# pdb-12-50.net
KiCad netlist of a schematic drawn in EasyEDA Pro
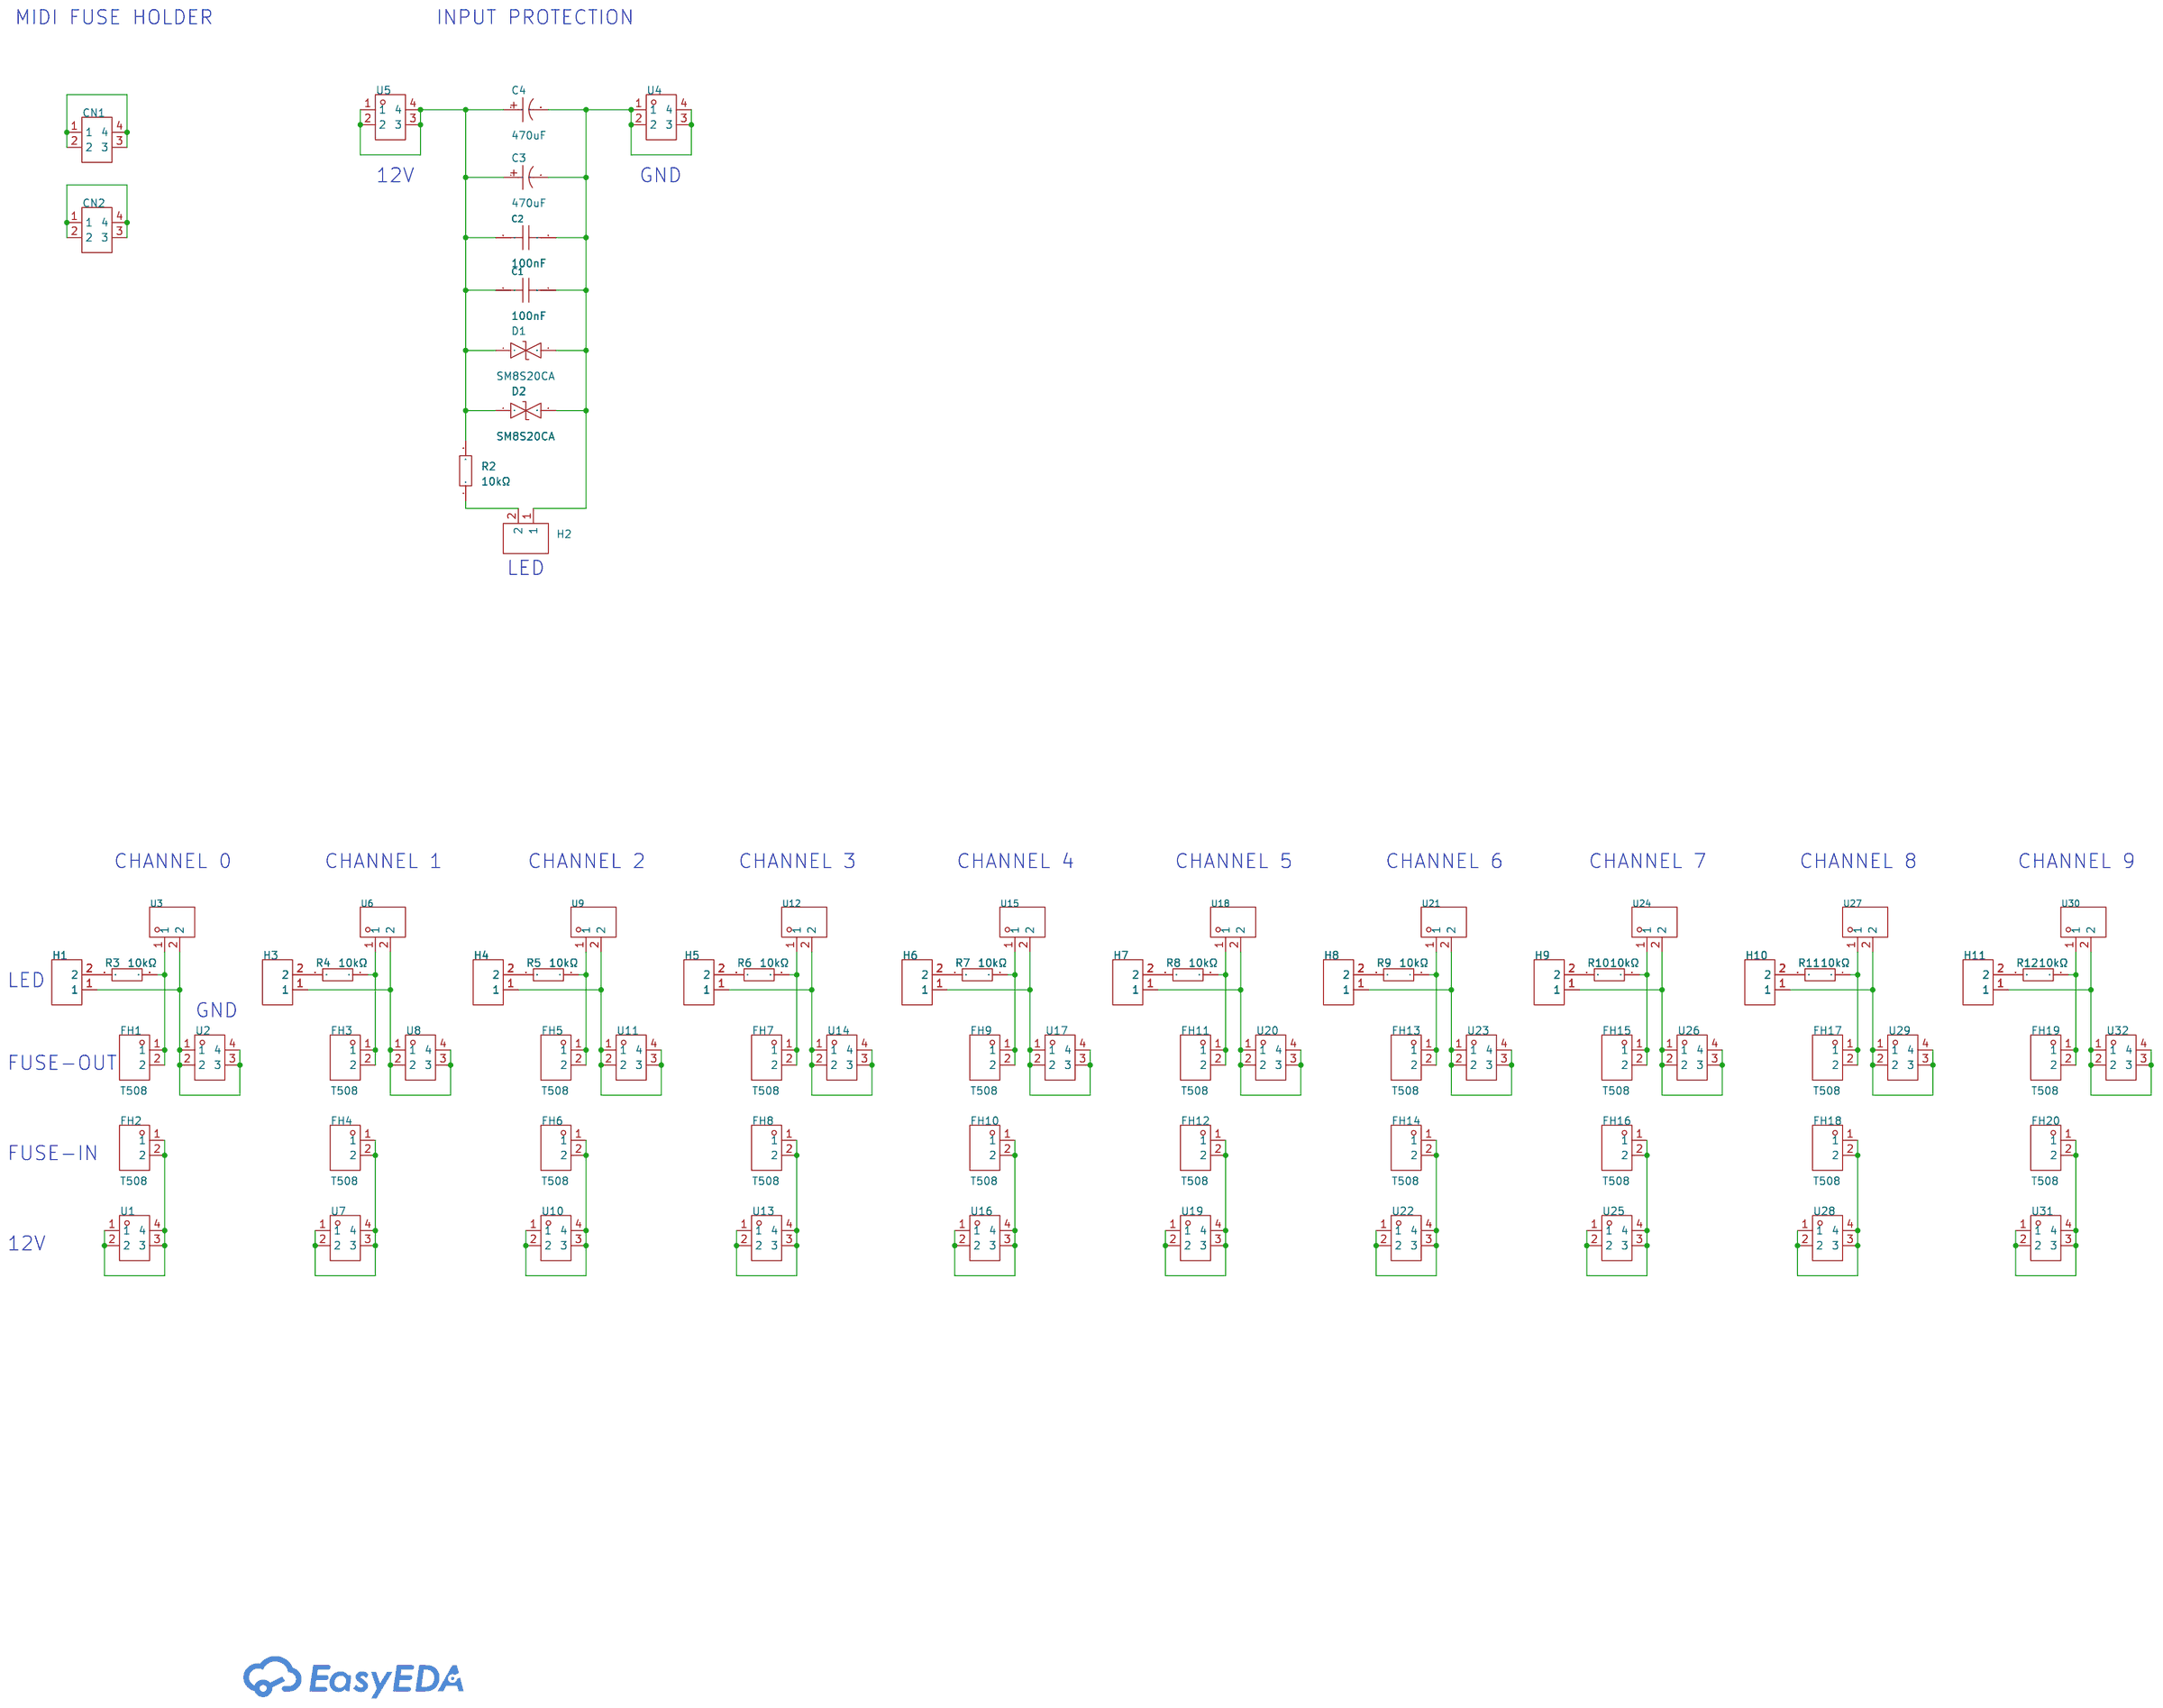
[diagram p0: schematic sheet]

(export (version "E")
  (design (tool "Eeschema 10.0.6"))
  (components
    (comp (ref "C1")
      (value "100nF")
      (footprint "easyedapro:C1210")
      (fields (field (name "Manufacturer Part") "1210B104K501CT") (field (name "Manufacturer") "Walsin(华新科)"))
      (libsource (lib "easyedapro") (part "1210B104K501CT"))
    )
    (comp (ref "C2")
      (value "100nF")
      (footprint "easyedapro:C1210")
      (fields (field (name "Manufacturer Part") "1210B104K501CT") (field (name "Manufacturer") "Walsin(华新科)"))
      (libsource (lib "easyedapro") (part "1210B104K501CT"))
    )
    (comp (ref "C3")
      (value "470uF")
      (footprint "easyedapro:CAP-TH_BD10.0-P5.00-D1.0-FD")
      (fields
        (field (name "Manufacturer Part") "50PX470MEFC10X20")
        (field (name "Manufacturer") "Rubycon(红宝石)")
      )
      (libsource (lib "easyedapro") (part "50PX470MEFC10X20"))
    )
    (comp (ref "C4")
      (value "470uF")
      (footprint "easyedapro:CAP-TH_BD10.0-P5.00-D1.0-FD")
      (fields
        (field (name "Manufacturer Part") "50PX470MEFC10X20")
        (field (name "Manufacturer") "Rubycon(红宝石)")
      )
      (libsource (lib "easyedapro") (part "50PX470MEFC10X20"))
    )
    (comp (ref "CN1")
      (value "1007035CL5")
      (footprint "easyedapro:CONN-TH_4P-L10.5-W10.0_1007035CL5")
      (fields (field (name "Manufacturer") "SAMZO(三佐)"))
      (libsource (lib "easyedapro") (part "1007035CL5"))
    )
    (comp (ref "CN2")
      (value "1007035CL5")
      (footprint "easyedapro:CONN-TH_4P-L10.5-W10.0_1007035CL5")
      (fields (field (name "Manufacturer") "SAMZO(三佐)"))
      (libsource (lib "easyedapro") (part "1007035CL5"))
    )
    (comp (ref "D1")
      (value "SM8S20CA")
      (footprint "easyedapro:DO-218AB_L13.5-W8.4-LS15.5-BI")
      (fields (field (name "Manufacturer") "DOWO(东沃)"))
      (libsource (lib "easyedapro") (part "SM8S20CA"))
    )
    (comp (ref "D2")
      (value "SM8S20CA")
      (footprint "easyedapro:DO-218AB_L13.5-W8.4-LS15.5-BI")
      (fields (field (name "Manufacturer") "DOWO(东沃)"))
      (libsource (lib "easyedapro") (part "SM8S20CA"))
    )
    (comp (ref "FH1")
      (value "T508")
      (footprint "easyedapro:CONN-TH_T508")
      (description "Current Rating:30A")
      (fields (field (name "Manufacturer") "XFCN(兴飞)"))
      (libsource (lib "easyedapro") (part "T508"))
    )
    (comp (ref "FH2")
      (value "T508")
      (footprint "easyedapro:CONN-TH_T508")
      (description "Current Rating:30A")
      (fields (field (name "Manufacturer") "XFCN(兴飞)"))
      (libsource (lib "easyedapro") (part "T508"))
    )
    (comp (ref "FH3")
      (value "T508")
      (footprint "easyedapro:CONN-TH_T508")
      (description "Current Rating:30A")
      (fields (field (name "Manufacturer") "XFCN(兴飞)"))
      (libsource (lib "easyedapro") (part "T508"))
    )
    (comp (ref "FH4")
      (value "T508")
      (footprint "easyedapro:CONN-TH_T508")
      (description "Current Rating:30A")
      (fields (field (name "Manufacturer") "XFCN(兴飞)"))
      (libsource (lib "easyedapro") (part "T508"))
    )
    (comp (ref "FH5")
      (value "T508")
      (footprint "easyedapro:CONN-TH_T508")
      (description "Current Rating:30A")
      (fields (field (name "Manufacturer") "XFCN(兴飞)"))
      (libsource (lib "easyedapro") (part "T508"))
    )
    (comp (ref "FH6")
      (value "T508")
      (footprint "easyedapro:CONN-TH_T508")
      (description "Current Rating:30A")
      (fields (field (name "Manufacturer") "XFCN(兴飞)"))
      (libsource (lib "easyedapro") (part "T508"))
    )
    (comp (ref "FH7")
      (value "T508")
      (footprint "easyedapro:CONN-TH_T508")
      (description "Current Rating:30A")
      (fields (field (name "Manufacturer") "XFCN(兴飞)"))
      (libsource (lib "easyedapro") (part "T508"))
    )
    (comp (ref "FH8")
      (value "T508")
      (footprint "easyedapro:CONN-TH_T508")
      (description "Current Rating:30A")
      (fields (field (name "Manufacturer") "XFCN(兴飞)"))
      (libsource (lib "easyedapro") (part "T508"))
    )
    (comp (ref "FH9")
      (value "T508")
      (footprint "easyedapro:CONN-TH_T508")
      (description "Current Rating:30A")
      (fields (field (name "Manufacturer") "XFCN(兴飞)"))
      (libsource (lib "easyedapro") (part "T508"))
    )
    (comp (ref "FH10")
      (value "T508")
      (footprint "easyedapro:CONN-TH_T508")
      (description "Current Rating:30A")
      (fields (field (name "Manufacturer") "XFCN(兴飞)"))
      (libsource (lib "easyedapro") (part "T508"))
    )
    (comp (ref "FH11")
      (value "T508")
      (footprint "easyedapro:CONN-TH_T508")
      (description "Current Rating:30A")
      (fields (field (name "Manufacturer") "XFCN(兴飞)"))
      (libsource (lib "easyedapro") (part "T508"))
    )
    (comp (ref "FH12")
      (value "T508")
      (footprint "easyedapro:CONN-TH_T508")
      (description "Current Rating:30A")
      (fields (field (name "Manufacturer") "XFCN(兴飞)"))
      (libsource (lib "easyedapro") (part "T508"))
    )
    (comp (ref "FH13")
      (value "T508")
      (footprint "easyedapro:CONN-TH_T508")
      (description "Current Rating:30A")
      (fields (field (name "Manufacturer") "XFCN(兴飞)"))
      (libsource (lib "easyedapro") (part "T508"))
    )
    (comp (ref "FH14")
      (value "T508")
      (footprint "easyedapro:CONN-TH_T508")
      (description "Current Rating:30A")
      (fields (field (name "Manufacturer") "XFCN(兴飞)"))
      (libsource (lib "easyedapro") (part "T508"))
    )
    (comp (ref "FH15")
      (value "T508")
      (footprint "easyedapro:CONN-TH_T508")
      (description "Current Rating:30A")
      (fields (field (name "Manufacturer") "XFCN(兴飞)"))
      (libsource (lib "easyedapro") (part "T508"))
    )
    (comp (ref "FH16")
      (value "T508")
      (footprint "easyedapro:CONN-TH_T508")
      (description "Current Rating:30A")
      (fields (field (name "Manufacturer") "XFCN(兴飞)"))
      (libsource (lib "easyedapro") (part "T508"))
    )
    (comp (ref "FH17")
      (value "T508")
      (footprint "easyedapro:CONN-TH_T508")
      (description "Current Rating:30A")
      (fields (field (name "Manufacturer") "XFCN(兴飞)"))
      (libsource (lib "easyedapro") (part "T508"))
    )
    (comp (ref "FH18")
      (value "T508")
      (footprint "easyedapro:CONN-TH_T508")
      (description "Current Rating:30A")
      (fields (field (name "Manufacturer") "XFCN(兴飞)"))
      (libsource (lib "easyedapro") (part "T508"))
    )
    (comp (ref "FH19")
      (value "T508")
      (footprint "easyedapro:CONN-TH_T508")
      (description "Current Rating:30A")
      (fields (field (name "Manufacturer") "XFCN(兴飞)"))
      (libsource (lib "easyedapro") (part "T508"))
    )
    (comp (ref "FH20")
      (value "T508")
      (footprint "easyedapro:CONN-TH_T508")
      (description "Current Rating:30A")
      (fields (field (name "Manufacturer") "XFCN(兴飞)"))
      (libsource (lib "easyedapro") (part "T508"))
    )
    (comp (ref "H1")
      (value "PZ254V-11-02P")
      (footprint "easyedapro:HDR-TH_2P-P2.54-V-M")
      (fields (field (name "Manufacturer") "XFCN(兴飞)"))
      (libsource (lib "easyedapro") (part "PZ254V-11-02P"))
    )
    (comp (ref "H2")
      (value "PZ254V-11-02P")
      (footprint "easyedapro:HDR-TH_2P-P2.54-V-M")
      (fields (field (name "Manufacturer") "XFCN(兴飞)"))
      (libsource (lib "easyedapro") (part "PZ254V-11-02P"))
    )
    (comp (ref "H3")
      (value "PZ254V-11-02P")
      (footprint "easyedapro:HDR-TH_2P-P2.54-V-M")
      (fields (field (name "Manufacturer") "XFCN(兴飞)"))
      (libsource (lib "easyedapro") (part "PZ254V-11-02P"))
    )
    (comp (ref "H4")
      (value "PZ254V-11-02P")
      (footprint "easyedapro:HDR-TH_2P-P2.54-V-M")
      (fields (field (name "Manufacturer") "XFCN(兴飞)"))
      (libsource (lib "easyedapro") (part "PZ254V-11-02P"))
    )
    (comp (ref "H5")
      (value "PZ254V-11-02P")
      (footprint "easyedapro:HDR-TH_2P-P2.54-V-M")
      (fields (field (name "Manufacturer") "XFCN(兴飞)"))
      (libsource (lib "easyedapro") (part "PZ254V-11-02P"))
    )
    (comp (ref "H6")
      (value "PZ254V-11-02P")
      (footprint "easyedapro:HDR-TH_2P-P2.54-V-M")
      (fields (field (name "Manufacturer") "XFCN(兴飞)"))
      (libsource (lib "easyedapro") (part "PZ254V-11-02P"))
    )
    (comp (ref "H7")
      (value "PZ254V-11-02P")
      (footprint "easyedapro:HDR-TH_2P-P2.54-V-M")
      (fields (field (name "Manufacturer") "XFCN(兴飞)"))
      (libsource (lib "easyedapro") (part "PZ254V-11-02P"))
    )
    (comp (ref "H8")
      (value "PZ254V-11-02P")
      (footprint "easyedapro:HDR-TH_2P-P2.54-V-M")
      (fields (field (name "Manufacturer") "XFCN(兴飞)"))
      (libsource (lib "easyedapro") (part "PZ254V-11-02P"))
    )
    (comp (ref "H9")
      (value "PZ254V-11-02P")
      (footprint "easyedapro:HDR-TH_2P-P2.54-V-M")
      (fields (field (name "Manufacturer") "XFCN(兴飞)"))
      (libsource (lib "easyedapro") (part "PZ254V-11-02P"))
    )
    (comp (ref "H10")
      (value "PZ254V-11-02P")
      (footprint "easyedapro:HDR-TH_2P-P2.54-V-M")
      (fields (field (name "Manufacturer") "XFCN(兴飞)"))
      (libsource (lib "easyedapro") (part "PZ254V-11-02P"))
    )
    (comp (ref "H11")
      (value "PZ254V-11-02P")
      (footprint "easyedapro:HDR-TH_2P-P2.54-V-M")
      (fields (field (name "Manufacturer") "XFCN(兴飞)"))
      (libsource (lib "easyedapro") (part "PZ254V-11-02P"))
    )
    (comp (ref "R2")
      (value "10kΩ")
      (footprint "easyedapro:RES-TH_BD1.8-L3.2-P7.20-D0.4")
      (fields
        (field (name "Manufacturer Part") "1206W4F1002T5E")
        (field (name "Manufacturer") "UNI-ROYAL(厚声)")
      )
      (libsource (lib "easyedapro") (part "Res"))
    )
    (comp (ref "R3")
      (value "10kΩ")
      (footprint "easyedapro:RES-TH_BD1.8-L3.2-P7.20-D0.4")
      (fields
        (field (name "Manufacturer Part") "1206W4F1002T5E")
        (field (name "Manufacturer") "UNI-ROYAL(厚声)")
      )
      (libsource (lib "easyedapro") (part "Res"))
    )
    (comp (ref "R4")
      (value "10kΩ")
      (footprint "easyedapro:RES-TH_BD1.8-L3.2-P7.20-D0.4")
      (fields
        (field (name "Manufacturer Part") "1206W4F1002T5E")
        (field (name "Manufacturer") "UNI-ROYAL(厚声)")
      )
      (libsource (lib "easyedapro") (part "Res"))
    )
    (comp (ref "R5")
      (value "10kΩ")
      (footprint "easyedapro:RES-TH_BD1.8-L3.2-P7.20-D0.4")
      (fields
        (field (name "Manufacturer Part") "1206W4F1002T5E")
        (field (name "Manufacturer") "UNI-ROYAL(厚声)")
      )
      (libsource (lib "easyedapro") (part "Res"))
    )
    (comp (ref "R6")
      (value "10kΩ")
      (footprint "easyedapro:RES-TH_BD1.8-L3.2-P7.20-D0.4")
      (fields
        (field (name "Manufacturer Part") "1206W4F1002T5E")
        (field (name "Manufacturer") "UNI-ROYAL(厚声)")
      )
      (libsource (lib "easyedapro") (part "Res"))
    )
    (comp (ref "R7")
      (value "10kΩ")
      (footprint "easyedapro:RES-TH_BD1.8-L3.2-P7.20-D0.4")
      (fields
        (field (name "Manufacturer Part") "1206W4F1002T5E")
        (field (name "Manufacturer") "UNI-ROYAL(厚声)")
      )
      (libsource (lib "easyedapro") (part "Res"))
    )
    (comp (ref "R8")
      (value "10kΩ")
      (footprint "easyedapro:RES-TH_BD1.8-L3.2-P7.20-D0.4")
      (fields
        (field (name "Manufacturer Part") "1206W4F1002T5E")
        (field (name "Manufacturer") "UNI-ROYAL(厚声)")
      )
      (libsource (lib "easyedapro") (part "Res"))
    )
    (comp (ref "R9")
      (value "10kΩ")
      (footprint "easyedapro:RES-TH_BD1.8-L3.2-P7.20-D0.4")
      (fields
        (field (name "Manufacturer Part") "1206W4F1002T5E")
        (field (name "Manufacturer") "UNI-ROYAL(厚声)")
      )
      (libsource (lib "easyedapro") (part "Res"))
    )
    (comp (ref "R10")
      (value "10kΩ")
      (footprint "easyedapro:RES-TH_BD1.8-L3.2-P7.20-D0.4")
      (fields
        (field (name "Manufacturer Part") "1206W4F1002T5E")
        (field (name "Manufacturer") "UNI-ROYAL(厚声)")
      )
      (libsource (lib "easyedapro") (part "Res"))
    )
    (comp (ref "R11")
      (value "10kΩ")
      (footprint "easyedapro:RES-TH_BD1.8-L3.2-P7.20-D0.4")
      (fields
        (field (name "Manufacturer Part") "1206W4F1002T5E")
        (field (name "Manufacturer") "UNI-ROYAL(厚声)")
      )
      (libsource (lib "easyedapro") (part "Res"))
    )
    (comp (ref "R12")
      (value "10kΩ")
      (footprint "easyedapro:RES-TH_BD1.8-L3.2-P7.20-D0.4")
      (fields
        (field (name "Manufacturer Part") "1206W4F1002T5E")
        (field (name "Manufacturer") "UNI-ROYAL(厚声)")
      )
      (libsource (lib "easyedapro") (part "Res"))
    )
    (comp (ref "U1")
      (value "66540S0M3")
      (footprint "easyedapro:SMD_66540S0M3")
      (fields (field (name "Manufacturer") "SAMZO(三佐)"))
      (libsource (lib "easyedapro") (part "66540S0M3"))
    )
    (comp (ref "U2")
      (value "66540S0M3")
      (footprint "easyedapro:SMD_66540S0M3")
      (fields (field (name "Manufacturer") "SAMZO(三佐)"))
      (libsource (lib "easyedapro") (part "66540S0M3"))
    )
    (comp (ref "U3")
      (value "KF635-6.35-2P")
      (footprint "easyedapro:CONN-TH_P6.35_KF635-6.35-2P")
      (fields (field (name "Manufacturer") "KEFA(科发)"))
      (libsource (lib "easyedapro") (part "KF635-6.35-2P"))
    )
    (comp (ref "U4")
      (value "66540S0M3")
      (footprint "easyedapro:SMD_66540S0M3")
      (fields (field (name "Manufacturer") "SAMZO(三佐)"))
      (libsource (lib "easyedapro") (part "66540S0M3"))
    )
    (comp (ref "U5")
      (value "66540S0M3")
      (footprint "easyedapro:SMD_66540S0M3")
      (fields (field (name "Manufacturer") "SAMZO(三佐)"))
      (libsource (lib "easyedapro") (part "66540S0M3"))
    )
    (comp (ref "U6")
      (value "KF635-6.35-2P")
      (footprint "easyedapro:CONN-TH_P6.35_KF635-6.35-2P")
      (fields (field (name "Manufacturer") "KEFA(科发)"))
      (libsource (lib "easyedapro") (part "KF635-6.35-2P"))
    )
    (comp (ref "U7")
      (value "66540S0M3")
      (footprint "easyedapro:SMD_66540S0M3")
      (fields (field (name "Manufacturer") "SAMZO(三佐)"))
      (libsource (lib "easyedapro") (part "66540S0M3"))
    )
    (comp (ref "U8")
      (value "66540S0M3")
      (footprint "easyedapro:SMD_66540S0M3")
      (fields (field (name "Manufacturer") "SAMZO(三佐)"))
      (libsource (lib "easyedapro") (part "66540S0M3"))
    )
    (comp (ref "U9")
      (value "KF635-6.35-2P")
      (footprint "easyedapro:CONN-TH_P6.35_KF635-6.35-2P")
      (fields (field (name "Manufacturer") "KEFA(科发)"))
      (libsource (lib "easyedapro") (part "KF635-6.35-2P"))
    )
    (comp (ref "U10")
      (value "66540S0M3")
      (footprint "easyedapro:SMD_66540S0M3")
      (fields (field (name "Manufacturer") "SAMZO(三佐)"))
      (libsource (lib "easyedapro") (part "66540S0M3"))
    )
    (comp (ref "U11")
      (value "66540S0M3")
      (footprint "easyedapro:SMD_66540S0M3")
      (fields (field (name "Manufacturer") "SAMZO(三佐)"))
      (libsource (lib "easyedapro") (part "66540S0M3"))
    )
    (comp (ref "U12")
      (value "KF635-6.35-2P")
      (footprint "easyedapro:CONN-TH_P6.35_KF635-6.35-2P")
      (fields (field (name "Manufacturer") "KEFA(科发)"))
      (libsource (lib "easyedapro") (part "KF635-6.35-2P"))
    )
    (comp (ref "U13")
      (value "66540S0M3")
      (footprint "easyedapro:SMD_66540S0M3")
      (fields (field (name "Manufacturer") "SAMZO(三佐)"))
      (libsource (lib "easyedapro") (part "66540S0M3"))
    )
    (comp (ref "U14")
      (value "66540S0M3")
      (footprint "easyedapro:SMD_66540S0M3")
      (fields (field (name "Manufacturer") "SAMZO(三佐)"))
      (libsource (lib "easyedapro") (part "66540S0M3"))
    )
    (comp (ref "U15")
      (value "KF635-6.35-2P")
      (footprint "easyedapro:CONN-TH_P6.35_KF635-6.35-2P")
      (fields (field (name "Manufacturer") "KEFA(科发)"))
      (libsource (lib "easyedapro") (part "KF635-6.35-2P"))
    )
    (comp (ref "U16")
      (value "66540S0M3")
      (footprint "easyedapro:SMD_66540S0M3")
      (fields (field (name "Manufacturer") "SAMZO(三佐)"))
      (libsource (lib "easyedapro") (part "66540S0M3"))
    )
    (comp (ref "U17")
      (value "66540S0M3")
      (footprint "easyedapro:SMD_66540S0M3")
      (fields (field (name "Manufacturer") "SAMZO(三佐)"))
      (libsource (lib "easyedapro") (part "66540S0M3"))
    )
    (comp (ref "U18")
      (value "KF635-6.35-2P")
      (footprint "easyedapro:CONN-TH_P6.35_KF635-6.35-2P")
      (fields (field (name "Manufacturer") "KEFA(科发)"))
      (libsource (lib "easyedapro") (part "KF635-6.35-2P"))
    )
    (comp (ref "U19")
      (value "66540S0M3")
      (footprint "easyedapro:SMD_66540S0M3")
      (fields (field (name "Manufacturer") "SAMZO(三佐)"))
      (libsource (lib "easyedapro") (part "66540S0M3"))
    )
    (comp (ref "U20")
      (value "66540S0M3")
      (footprint "easyedapro:SMD_66540S0M3")
      (fields (field (name "Manufacturer") "SAMZO(三佐)"))
      (libsource (lib "easyedapro") (part "66540S0M3"))
    )
    (comp (ref "U21")
      (value "KF635-6.35-2P")
      (footprint "easyedapro:CONN-TH_P6.35_KF635-6.35-2P")
      (fields (field (name "Manufacturer") "KEFA(科发)"))
      (libsource (lib "easyedapro") (part "KF635-6.35-2P"))
    )
    (comp (ref "U22")
      (value "66540S0M3")
      (footprint "easyedapro:SMD_66540S0M3")
      (fields (field (name "Manufacturer") "SAMZO(三佐)"))
      (libsource (lib "easyedapro") (part "66540S0M3"))
    )
    (comp (ref "U23")
      (value "66540S0M3")
      (footprint "easyedapro:SMD_66540S0M3")
      (fields (field (name "Manufacturer") "SAMZO(三佐)"))
      (libsource (lib "easyedapro") (part "66540S0M3"))
    )
    (comp (ref "U24")
      (value "KF635-6.35-2P")
      (footprint "easyedapro:CONN-TH_P6.35_KF635-6.35-2P")
      (fields (field (name "Manufacturer") "KEFA(科发)"))
      (libsource (lib "easyedapro") (part "KF635-6.35-2P"))
    )
    (comp (ref "U25")
      (value "66540S0M3")
      (footprint "easyedapro:SMD_66540S0M3")
      (fields (field (name "Manufacturer") "SAMZO(三佐)"))
      (libsource (lib "easyedapro") (part "66540S0M3"))
    )
    (comp (ref "U26")
      (value "66540S0M3")
      (footprint "easyedapro:SMD_66540S0M3")
      (fields (field (name "Manufacturer") "SAMZO(三佐)"))
      (libsource (lib "easyedapro") (part "66540S0M3"))
    )
    (comp (ref "U27")
      (value "KF635-6.35-2P")
      (footprint "easyedapro:CONN-TH_P6.35_KF635-6.35-2P")
      (fields (field (name "Manufacturer") "KEFA(科发)"))
      (libsource (lib "easyedapro") (part "KF635-6.35-2P"))
    )
    (comp (ref "U28")
      (value "66540S0M3")
      (footprint "easyedapro:SMD_66540S0M3")
      (fields (field (name "Manufacturer") "SAMZO(三佐)"))
      (libsource (lib "easyedapro") (part "66540S0M3"))
    )
    (comp (ref "U29")
      (value "66540S0M3")
      (footprint "easyedapro:SMD_66540S0M3")
      (fields (field (name "Manufacturer") "SAMZO(三佐)"))
      (libsource (lib "easyedapro") (part "66540S0M3"))
    )
    (comp (ref "U30")
      (value "KF635-6.35-2P")
      (footprint "easyedapro:CONN-TH_P6.35_KF635-6.35-2P")
      (fields (field (name "Manufacturer") "KEFA(科发)"))
      (libsource (lib "easyedapro") (part "KF635-6.35-2P"))
    )
    (comp (ref "U31")
      (value "66540S0M3")
      (footprint "easyedapro:SMD_66540S0M3")
      (fields (field (name "Manufacturer") "SAMZO(三佐)"))
      (libsource (lib "easyedapro") (part "66540S0M3"))
    )
    (comp (ref "U32")
      (value "66540S0M3")
      (footprint "easyedapro:SMD_66540S0M3")
      (fields (field (name "Manufacturer") "SAMZO(三佐)"))
      (libsource (lib "easyedapro") (part "66540S0M3"))
    )
  )
  (nets
    (net (code "1") (name "Net-(C1-Pad1)") (class "Default")
      (node (ref "C1") (pin "1") (pinfunction "1_1") (pintype "input"))
      (node (ref "C2") (pin "1") (pinfunction "1_1") (pintype "input"))
      (node (ref "C3") (pin "2") (pinfunction "2_2") (pintype "input"))
      (node (ref "C4") (pin "2") (pinfunction "2_2") (pintype "input"))
      (node (ref "D1") (pin "2") (pinfunction "2_2") (pintype "unspecified"))
      (node (ref "D2") (pin "2") (pinfunction "2_2") (pintype "unspecified"))
      (node (ref "H2") (pin "1") (pinfunction "1_1") (pintype "unspecified"))
      (node (ref "U4") (pin "1") (pinfunction "1_1") (pintype "unspecified"))
      (node (ref "U4") (pin "2") (pinfunction "2_2") (pintype "unspecified"))
      (node (ref "U4") (pin "3") (pinfunction "3_3") (pintype "unspecified"))
      (node (ref "U4") (pin "4") (pinfunction "4_4") (pintype "unspecified"))
    )
    (net (code "2") (name "Net-(C1-Pad2)") (class "Default")
      (node (ref "C1") (pin "2") (pinfunction "2_2") (pintype "input"))
      (node (ref "C2") (pin "2") (pinfunction "2_2") (pintype "input"))
      (node (ref "C3") (pin "1") (pinfunction "1_1") (pintype "input"))
      (node (ref "C4") (pin "1") (pinfunction "1_1") (pintype "input"))
      (node (ref "D1") (pin "1") (pinfunction "1_1") (pintype "unspecified"))
      (node (ref "D2") (pin "1") (pinfunction "1_1") (pintype "unspecified"))
      (node (ref "R2") (pin "2") (pinfunction "2_2") (pintype "input"))
      (node (ref "U5") (pin "1") (pinfunction "1_1") (pintype "unspecified"))
      (node (ref "U5") (pin "2") (pinfunction "2_2") (pintype "unspecified"))
      (node (ref "U5") (pin "3") (pinfunction "3_3") (pintype "unspecified"))
      (node (ref "U5") (pin "4") (pinfunction "4_4") (pintype "unspecified"))
    )
    (net (code "3") (name "Net-(CN1-Pad1)") (class "Default")
      (node (ref "CN1") (pin "1") (pinfunction "1_1") (pintype "unspecified"))
      (node (ref "CN1") (pin "2") (pinfunction "2_2") (pintype "unspecified"))
      (node (ref "CN1") (pin "3") (pinfunction "3_3") (pintype "unspecified"))
      (node (ref "CN1") (pin "4") (pinfunction "4_4") (pintype "unspecified"))
    )
    (net (code "4") (name "Net-(CN2-Pad1)") (class "Default")
      (node (ref "CN2") (pin "1") (pinfunction "1_1") (pintype "unspecified"))
      (node (ref "CN2") (pin "2") (pinfunction "2_2") (pintype "unspecified"))
      (node (ref "CN2") (pin "3") (pinfunction "3_3") (pintype "unspecified"))
      (node (ref "CN2") (pin "4") (pinfunction "4_4") (pintype "unspecified"))
    )
    (net (code "5") (name "Net-(FH1-Pad1)") (class "Default")
      (node (ref "FH1") (pin "1") (pinfunction "1_1") (pintype "unspecified"))
      (node (ref "FH1") (pin "2") (pinfunction "2_2") (pintype "unspecified"))
      (node (ref "R3") (pin "1") (pinfunction "1_1") (pintype "input"))
      (node (ref "U3") (pin "1") (pinfunction "1_1") (pintype "input"))
    )
    (net (code "6") (name "Net-(FH2-Pad1)") (class "Default")
      (node (ref "FH2") (pin "1") (pinfunction "1_1") (pintype "unspecified"))
      (node (ref "FH2") (pin "2") (pinfunction "2_2") (pintype "unspecified"))
      (node (ref "U1") (pin "1") (pinfunction "1_1") (pintype "unspecified"))
      (node (ref "U1") (pin "2") (pinfunction "2_2") (pintype "unspecified"))
      (node (ref "U1") (pin "3") (pinfunction "3_3") (pintype "unspecified"))
      (node (ref "U1") (pin "4") (pinfunction "4_4") (pintype "unspecified"))
    )
    (net (code "7") (name "Net-(FH3-Pad1)") (class "Default")
      (node (ref "FH3") (pin "1") (pinfunction "1_1") (pintype "unspecified"))
      (node (ref "FH3") (pin "2") (pinfunction "2_2") (pintype "unspecified"))
      (node (ref "R4") (pin "1") (pinfunction "1_1") (pintype "input"))
      (node (ref "U6") (pin "1") (pinfunction "1_1") (pintype "input"))
    )
    (net (code "8") (name "Net-(FH4-Pad1)") (class "Default")
      (node (ref "FH4") (pin "1") (pinfunction "1_1") (pintype "unspecified"))
      (node (ref "FH4") (pin "2") (pinfunction "2_2") (pintype "unspecified"))
      (node (ref "U7") (pin "1") (pinfunction "1_1") (pintype "unspecified"))
      (node (ref "U7") (pin "2") (pinfunction "2_2") (pintype "unspecified"))
      (node (ref "U7") (pin "3") (pinfunction "3_3") (pintype "unspecified"))
      (node (ref "U7") (pin "4") (pinfunction "4_4") (pintype "unspecified"))
    )
    (net (code "9") (name "Net-(FH5-Pad1)") (class "Default")
      (node (ref "FH5") (pin "1") (pinfunction "1_1") (pintype "unspecified"))
      (node (ref "FH5") (pin "2") (pinfunction "2_2") (pintype "unspecified"))
      (node (ref "R5") (pin "1") (pinfunction "1_1") (pintype "input"))
      (node (ref "U9") (pin "1") (pinfunction "1_1") (pintype "input"))
    )
    (net (code "10") (name "Net-(FH6-Pad1)") (class "Default")
      (node (ref "FH6") (pin "1") (pinfunction "1_1") (pintype "unspecified"))
      (node (ref "FH6") (pin "2") (pinfunction "2_2") (pintype "unspecified"))
      (node (ref "U10") (pin "1") (pinfunction "1_1") (pintype "unspecified"))
      (node (ref "U10") (pin "2") (pinfunction "2_2") (pintype "unspecified"))
      (node (ref "U10") (pin "3") (pinfunction "3_3") (pintype "unspecified"))
      (node (ref "U10") (pin "4") (pinfunction "4_4") (pintype "unspecified"))
    )
    (net (code "11") (name "Net-(FH7-Pad1)") (class "Default")
      (node (ref "FH7") (pin "1") (pinfunction "1_1") (pintype "unspecified"))
      (node (ref "FH7") (pin "2") (pinfunction "2_2") (pintype "unspecified"))
      (node (ref "R6") (pin "1") (pinfunction "1_1") (pintype "input"))
      (node (ref "U12") (pin "1") (pinfunction "1_1") (pintype "input"))
    )
    (net (code "12") (name "Net-(FH8-Pad1)") (class "Default")
      (node (ref "FH8") (pin "1") (pinfunction "1_1") (pintype "unspecified"))
      (node (ref "FH8") (pin "2") (pinfunction "2_2") (pintype "unspecified"))
      (node (ref "U13") (pin "1") (pinfunction "1_1") (pintype "unspecified"))
      (node (ref "U13") (pin "2") (pinfunction "2_2") (pintype "unspecified"))
      (node (ref "U13") (pin "3") (pinfunction "3_3") (pintype "unspecified"))
      (node (ref "U13") (pin "4") (pinfunction "4_4") (pintype "unspecified"))
    )
    (net (code "13") (name "Net-(FH9-Pad1)") (class "Default")
      (node (ref "FH9") (pin "1") (pinfunction "1_1") (pintype "unspecified"))
      (node (ref "FH9") (pin "2") (pinfunction "2_2") (pintype "unspecified"))
      (node (ref "R7") (pin "1") (pinfunction "1_1") (pintype "input"))
      (node (ref "U15") (pin "1") (pinfunction "1_1") (pintype "input"))
    )
    (net (code "14") (name "Net-(FH10-Pad1)") (class "Default")
      (node (ref "FH10") (pin "1") (pinfunction "1_1") (pintype "unspecified"))
      (node (ref "FH10") (pin "2") (pinfunction "2_2") (pintype "unspecified"))
      (node (ref "U16") (pin "1") (pinfunction "1_1") (pintype "unspecified"))
      (node (ref "U16") (pin "2") (pinfunction "2_2") (pintype "unspecified"))
      (node (ref "U16") (pin "3") (pinfunction "3_3") (pintype "unspecified"))
      (node (ref "U16") (pin "4") (pinfunction "4_4") (pintype "unspecified"))
    )
    (net (code "15") (name "Net-(FH11-Pad1)") (class "Default")
      (node (ref "FH11") (pin "1") (pinfunction "1_1") (pintype "unspecified"))
      (node (ref "FH11") (pin "2") (pinfunction "2_2") (pintype "unspecified"))
      (node (ref "R8") (pin "1") (pinfunction "1_1") (pintype "input"))
      (node (ref "U18") (pin "1") (pinfunction "1_1") (pintype "input"))
    )
    (net (code "16") (name "Net-(FH12-Pad1)") (class "Default")
      (node (ref "FH12") (pin "1") (pinfunction "1_1") (pintype "unspecified"))
      (node (ref "FH12") (pin "2") (pinfunction "2_2") (pintype "unspecified"))
      (node (ref "U19") (pin "1") (pinfunction "1_1") (pintype "unspecified"))
      (node (ref "U19") (pin "2") (pinfunction "2_2") (pintype "unspecified"))
      (node (ref "U19") (pin "3") (pinfunction "3_3") (pintype "unspecified"))
      (node (ref "U19") (pin "4") (pinfunction "4_4") (pintype "unspecified"))
    )
    (net (code "17") (name "Net-(FH13-Pad1)") (class "Default")
      (node (ref "FH13") (pin "1") (pinfunction "1_1") (pintype "unspecified"))
      (node (ref "FH13") (pin "2") (pinfunction "2_2") (pintype "unspecified"))
      (node (ref "R9") (pin "1") (pinfunction "1_1") (pintype "input"))
      (node (ref "U21") (pin "1") (pinfunction "1_1") (pintype "input"))
    )
    (net (code "18") (name "Net-(FH14-Pad1)") (class "Default")
      (node (ref "FH14") (pin "1") (pinfunction "1_1") (pintype "unspecified"))
      (node (ref "FH14") (pin "2") (pinfunction "2_2") (pintype "unspecified"))
      (node (ref "U22") (pin "1") (pinfunction "1_1") (pintype "unspecified"))
      (node (ref "U22") (pin "2") (pinfunction "2_2") (pintype "unspecified"))
      (node (ref "U22") (pin "3") (pinfunction "3_3") (pintype "unspecified"))
      (node (ref "U22") (pin "4") (pinfunction "4_4") (pintype "unspecified"))
    )
    (net (code "19") (name "Net-(FH15-Pad1)") (class "Default")
      (node (ref "FH15") (pin "1") (pinfunction "1_1") (pintype "unspecified"))
      (node (ref "FH15") (pin "2") (pinfunction "2_2") (pintype "unspecified"))
      (node (ref "R10") (pin "1") (pinfunction "1_1") (pintype "input"))
      (node (ref "U24") (pin "1") (pinfunction "1_1") (pintype "input"))
    )
    (net (code "20") (name "Net-(FH16-Pad1)") (class "Default")
      (node (ref "FH16") (pin "1") (pinfunction "1_1") (pintype "unspecified"))
      (node (ref "FH16") (pin "2") (pinfunction "2_2") (pintype "unspecified"))
      (node (ref "U25") (pin "1") (pinfunction "1_1") (pintype "unspecified"))
      (node (ref "U25") (pin "2") (pinfunction "2_2") (pintype "unspecified"))
      (node (ref "U25") (pin "3") (pinfunction "3_3") (pintype "unspecified"))
      (node (ref "U25") (pin "4") (pinfunction "4_4") (pintype "unspecified"))
    )
    (net (code "21") (name "Net-(FH17-Pad1)") (class "Default")
      (node (ref "FH17") (pin "1") (pinfunction "1_1") (pintype "unspecified"))
      (node (ref "FH17") (pin "2") (pinfunction "2_2") (pintype "unspecified"))
      (node (ref "R11") (pin "1") (pinfunction "1_1") (pintype "input"))
      (node (ref "U27") (pin "1") (pinfunction "1_1") (pintype "input"))
    )
    (net (code "22") (name "Net-(FH18-Pad1)") (class "Default")
      (node (ref "FH18") (pin "1") (pinfunction "1_1") (pintype "unspecified"))
      (node (ref "FH18") (pin "2") (pinfunction "2_2") (pintype "unspecified"))
      (node (ref "U28") (pin "1") (pinfunction "1_1") (pintype "unspecified"))
      (node (ref "U28") (pin "2") (pinfunction "2_2") (pintype "unspecified"))
      (node (ref "U28") (pin "3") (pinfunction "3_3") (pintype "unspecified"))
      (node (ref "U28") (pin "4") (pinfunction "4_4") (pintype "unspecified"))
    )
    (net (code "23") (name "Net-(FH19-Pad1)") (class "Default")
      (node (ref "FH19") (pin "1") (pinfunction "1_1") (pintype "unspecified"))
      (node (ref "FH19") (pin "2") (pinfunction "2_2") (pintype "unspecified"))
      (node (ref "R12") (pin "1") (pinfunction "1_1") (pintype "input"))
      (node (ref "U30") (pin "1") (pinfunction "1_1") (pintype "input"))
    )
    (net (code "24") (name "Net-(FH20-Pad1)") (class "Default")
      (node (ref "FH20") (pin "1") (pinfunction "1_1") (pintype "unspecified"))
      (node (ref "FH20") (pin "2") (pinfunction "2_2") (pintype "unspecified"))
      (node (ref "U31") (pin "1") (pinfunction "1_1") (pintype "unspecified"))
      (node (ref "U31") (pin "2") (pinfunction "2_2") (pintype "unspecified"))
      (node (ref "U31") (pin "3") (pinfunction "3_3") (pintype "unspecified"))
      (node (ref "U31") (pin "4") (pinfunction "4_4") (pintype "unspecified"))
    )
    (net (code "25") (name "Net-(H1-Pad1)") (class "Default")
      (node (ref "H1") (pin "1") (pinfunction "1_1") (pintype "unspecified"))
      (node (ref "U2") (pin "1") (pinfunction "1_1") (pintype "unspecified"))
      (node (ref "U2") (pin "2") (pinfunction "2_2") (pintype "unspecified"))
      (node (ref "U2") (pin "3") (pinfunction "3_3") (pintype "unspecified"))
      (node (ref "U2") (pin "4") (pinfunction "4_4") (pintype "unspecified"))
      (node (ref "U3") (pin "2") (pinfunction "2_2") (pintype "input"))
    )
    (net (code "26") (name "Net-(H1-Pad2)") (class "Default")
      (node (ref "H1") (pin "2") (pinfunction "2_2") (pintype "unspecified"))
      (node (ref "R3") (pin "2") (pinfunction "2_2") (pintype "input"))
    )
    (net (code "27") (name "Net-(H2-Pad2)") (class "Default")
      (node (ref "H2") (pin "2") (pinfunction "2_2") (pintype "unspecified"))
      (node (ref "R2") (pin "1") (pinfunction "1_1") (pintype "input"))
    )
    (net (code "28") (name "Net-(H3-Pad1)") (class "Default")
      (node (ref "H3") (pin "1") (pinfunction "1_1") (pintype "unspecified"))
      (node (ref "U6") (pin "2") (pinfunction "2_2") (pintype "input"))
      (node (ref "U8") (pin "1") (pinfunction "1_1") (pintype "unspecified"))
      (node (ref "U8") (pin "2") (pinfunction "2_2") (pintype "unspecified"))
      (node (ref "U8") (pin "3") (pinfunction "3_3") (pintype "unspecified"))
      (node (ref "U8") (pin "4") (pinfunction "4_4") (pintype "unspecified"))
    )
    (net (code "29") (name "Net-(H3-Pad2)") (class "Default")
      (node (ref "H3") (pin "2") (pinfunction "2_2") (pintype "unspecified"))
      (node (ref "R4") (pin "2") (pinfunction "2_2") (pintype "input"))
    )
    (net (code "30") (name "Net-(H4-Pad1)") (class "Default")
      (node (ref "H4") (pin "1") (pinfunction "1_1") (pintype "unspecified"))
      (node (ref "U11") (pin "1") (pinfunction "1_1") (pintype "unspecified"))
      (node (ref "U11") (pin "2") (pinfunction "2_2") (pintype "unspecified"))
      (node (ref "U11") (pin "3") (pinfunction "3_3") (pintype "unspecified"))
      (node (ref "U11") (pin "4") (pinfunction "4_4") (pintype "unspecified"))
      (node (ref "U9") (pin "2") (pinfunction "2_2") (pintype "input"))
    )
    (net (code "31") (name "Net-(H4-Pad2)") (class "Default")
      (node (ref "H4") (pin "2") (pinfunction "2_2") (pintype "unspecified"))
      (node (ref "R5") (pin "2") (pinfunction "2_2") (pintype "input"))
    )
    (net (code "32") (name "Net-(H5-Pad1)") (class "Default")
      (node (ref "H5") (pin "1") (pinfunction "1_1") (pintype "unspecified"))
      (node (ref "U12") (pin "2") (pinfunction "2_2") (pintype "input"))
      (node (ref "U14") (pin "1") (pinfunction "1_1") (pintype "unspecified"))
      (node (ref "U14") (pin "2") (pinfunction "2_2") (pintype "unspecified"))
      (node (ref "U14") (pin "3") (pinfunction "3_3") (pintype "unspecified"))
      (node (ref "U14") (pin "4") (pinfunction "4_4") (pintype "unspecified"))
    )
    (net (code "33") (name "Net-(H5-Pad2)") (class "Default")
      (node (ref "H5") (pin "2") (pinfunction "2_2") (pintype "unspecified"))
      (node (ref "R6") (pin "2") (pinfunction "2_2") (pintype "input"))
    )
    (net (code "34") (name "Net-(H6-Pad1)") (class "Default")
      (node (ref "H6") (pin "1") (pinfunction "1_1") (pintype "unspecified"))
      (node (ref "U15") (pin "2") (pinfunction "2_2") (pintype "input"))
      (node (ref "U17") (pin "1") (pinfunction "1_1") (pintype "unspecified"))
      (node (ref "U17") (pin "2") (pinfunction "2_2") (pintype "unspecified"))
      (node (ref "U17") (pin "3") (pinfunction "3_3") (pintype "unspecified"))
      (node (ref "U17") (pin "4") (pinfunction "4_4") (pintype "unspecified"))
    )
    (net (code "35") (name "Net-(H6-Pad2)") (class "Default")
      (node (ref "H6") (pin "2") (pinfunction "2_2") (pintype "unspecified"))
      (node (ref "R7") (pin "2") (pinfunction "2_2") (pintype "input"))
    )
    (net (code "36") (name "Net-(H7-Pad1)") (class "Default")
      (node (ref "H7") (pin "1") (pinfunction "1_1") (pintype "unspecified"))
      (node (ref "U18") (pin "2") (pinfunction "2_2") (pintype "input"))
      (node (ref "U20") (pin "1") (pinfunction "1_1") (pintype "unspecified"))
      (node (ref "U20") (pin "2") (pinfunction "2_2") (pintype "unspecified"))
      (node (ref "U20") (pin "3") (pinfunction "3_3") (pintype "unspecified"))
      (node (ref "U20") (pin "4") (pinfunction "4_4") (pintype "unspecified"))
    )
    (net (code "37") (name "Net-(H7-Pad2)") (class "Default")
      (node (ref "H7") (pin "2") (pinfunction "2_2") (pintype "unspecified"))
      (node (ref "R8") (pin "2") (pinfunction "2_2") (pintype "input"))
    )
    (net (code "38") (name "Net-(H8-Pad1)") (class "Default")
      (node (ref "H8") (pin "1") (pinfunction "1_1") (pintype "unspecified"))
      (node (ref "U21") (pin "2") (pinfunction "2_2") (pintype "input"))
      (node (ref "U23") (pin "1") (pinfunction "1_1") (pintype "unspecified"))
      (node (ref "U23") (pin "2") (pinfunction "2_2") (pintype "unspecified"))
      (node (ref "U23") (pin "3") (pinfunction "3_3") (pintype "unspecified"))
      (node (ref "U23") (pin "4") (pinfunction "4_4") (pintype "unspecified"))
    )
    (net (code "39") (name "Net-(H8-Pad2)") (class "Default")
      (node (ref "H8") (pin "2") (pinfunction "2_2") (pintype "unspecified"))
      (node (ref "R9") (pin "2") (pinfunction "2_2") (pintype "input"))
    )
    (net (code "40") (name "Net-(H9-Pad1)") (class "Default")
      (node (ref "H9") (pin "1") (pinfunction "1_1") (pintype "unspecified"))
      (node (ref "U24") (pin "2") (pinfunction "2_2") (pintype "input"))
      (node (ref "U26") (pin "1") (pinfunction "1_1") (pintype "unspecified"))
      (node (ref "U26") (pin "2") (pinfunction "2_2") (pintype "unspecified"))
      (node (ref "U26") (pin "3") (pinfunction "3_3") (pintype "unspecified"))
      (node (ref "U26") (pin "4") (pinfunction "4_4") (pintype "unspecified"))
    )
    (net (code "41") (name "Net-(H9-Pad2)") (class "Default")
      (node (ref "H9") (pin "2") (pinfunction "2_2") (pintype "unspecified"))
      (node (ref "R10") (pin "2") (pinfunction "2_2") (pintype "input"))
    )
    (net (code "42") (name "Net-(H10-Pad1)") (class "Default")
      (node (ref "H10") (pin "1") (pinfunction "1_1") (pintype "unspecified"))
      (node (ref "U27") (pin "2") (pinfunction "2_2") (pintype "input"))
      (node (ref "U29") (pin "1") (pinfunction "1_1") (pintype "unspecified"))
      (node (ref "U29") (pin "2") (pinfunction "2_2") (pintype "unspecified"))
      (node (ref "U29") (pin "3") (pinfunction "3_3") (pintype "unspecified"))
      (node (ref "U29") (pin "4") (pinfunction "4_4") (pintype "unspecified"))
    )
    (net (code "43") (name "Net-(H10-Pad2)") (class "Default")
      (node (ref "H10") (pin "2") (pinfunction "2_2") (pintype "unspecified"))
      (node (ref "R11") (pin "2") (pinfunction "2_2") (pintype "input"))
    )
    (net (code "44") (name "Net-(H11-Pad1)") (class "Default")
      (node (ref "H11") (pin "1") (pinfunction "1_1") (pintype "unspecified"))
      (node (ref "U30") (pin "2") (pinfunction "2_2") (pintype "input"))
      (node (ref "U32") (pin "1") (pinfunction "1_1") (pintype "unspecified"))
      (node (ref "U32") (pin "2") (pinfunction "2_2") (pintype "unspecified"))
      (node (ref "U32") (pin "3") (pinfunction "3_3") (pintype "unspecified"))
      (node (ref "U32") (pin "4") (pinfunction "4_4") (pintype "unspecified"))
    )
    (net (code "45") (name "Net-(H11-Pad2)") (class "Default")
      (node (ref "H11") (pin "2") (pinfunction "2_2") (pintype "unspecified"))
      (node (ref "R12") (pin "2") (pinfunction "2_2") (pintype "input"))
    )
  )
)
